# mcu_core.net
KiCad netlist of a schematic drawn in Altium Designer
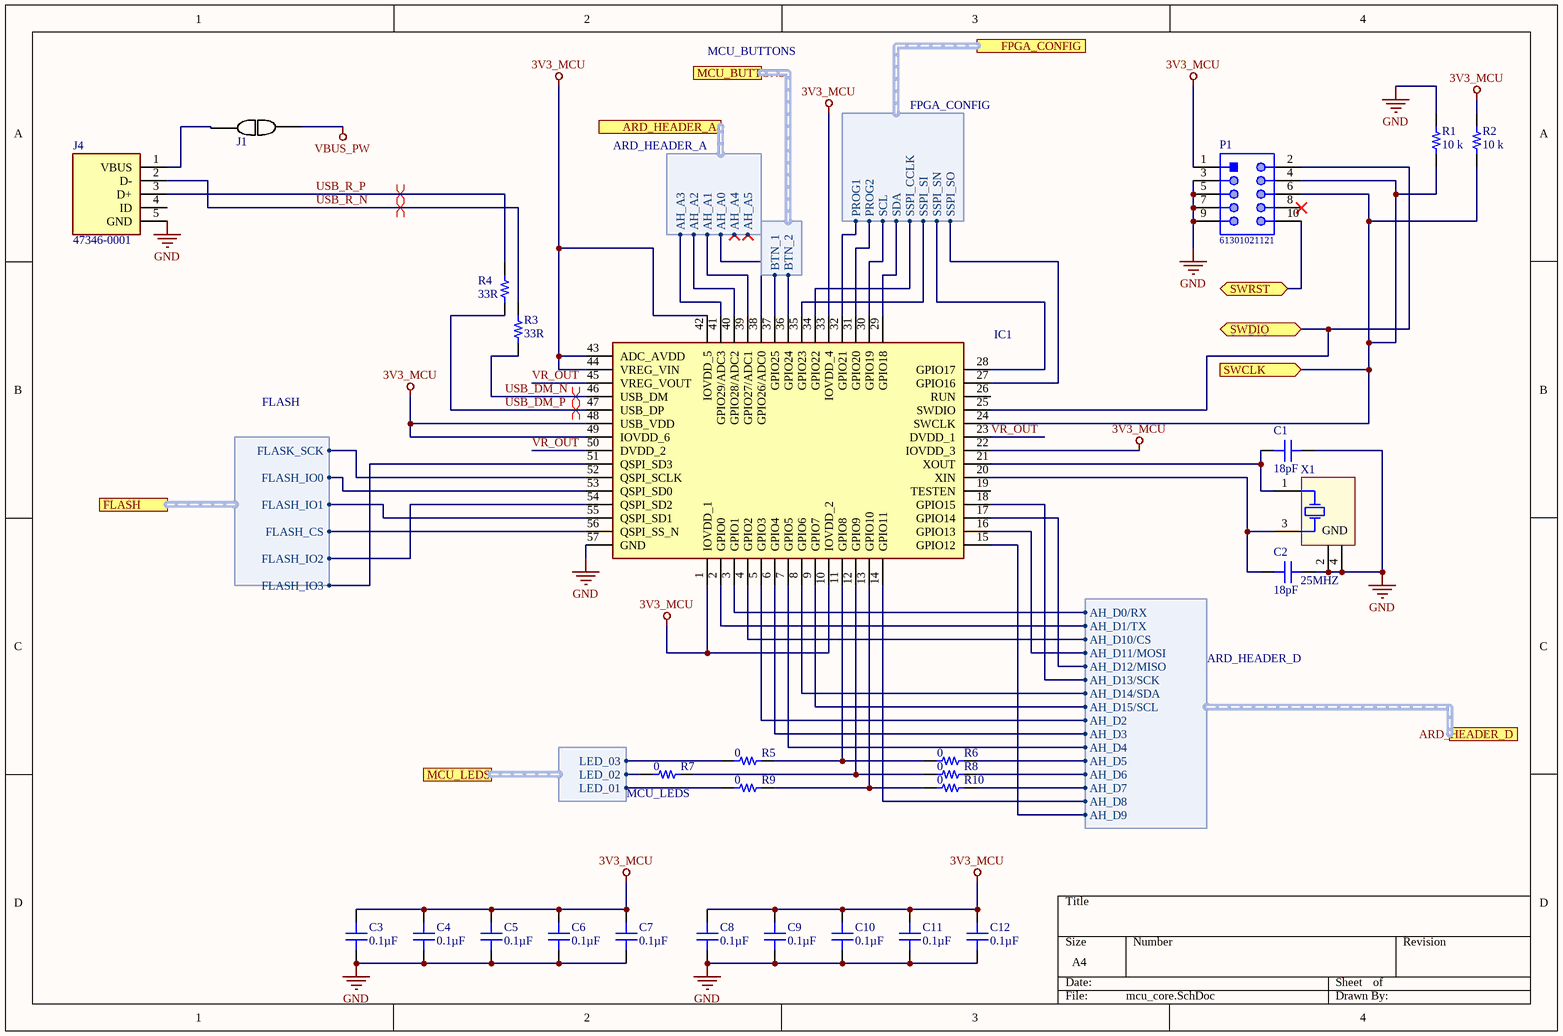
[diagram p0: mcu_core.SchDoc]

(export (version "E")
  (design (tool "Eeschema 10.0.6"))
  (components
    (comp (ref "C1")
      (value "18pF")
      (footprint "CAP 0603_1608")
      (description "CAP CER 18PF 10V C0G/NP0 0603")
      (fields
        (field (name "PART NUMBER") "VJ0603A180FXQCW1BC")
        (field (name "MANUFACTURER") "Vishay Vitramon")
      )
      (libsource (lib "Celestial Altium Library - altium_library (2)") (part "Capacitor"))
    )
    (comp (ref "C2")
      (value "18pF")
      (footprint "CAP 0603_1608")
      (description "CAP CER 18PF 10V C0G/NP0 0603")
      (fields
        (field (name "PART NUMBER") "VJ0603A180FXQCW1BC")
        (field (name "MANUFACTURER") "Vishay Vitramon")
      )
      (libsource (lib "Celestial Altium Library - altium_library (2)") (part "Capacitor"))
    )
    (comp (ref "C3")
      (value "0.1µF")
      (footprint "CAP 0603_1608")
      (description "CAP CER 0.1UF 50V X7R 0603")
      (fields (field (name "PART NUMBER") "C0603C104K5RAC7411") (field (name "MANUFACTURER") "KEMET"))
      (libsource (lib "Celestial Altium Library - altium_library (2)") (part "Capacitor"))
    )
    (comp (ref "C4")
      (value "0.1µF")
      (footprint "CAP 0603_1608")
      (description "CAP CER 0.1UF 50V X7R 0603")
      (fields (field (name "PART NUMBER") "C0603C104K5RAC7411") (field (name "MANUFACTURER") "KEMET"))
      (libsource (lib "Celestial Altium Library - altium_library (2)") (part "Capacitor"))
    )
    (comp (ref "C5")
      (value "0.1µF")
      (footprint "CAP 0603_1608")
      (description "CAP CER 0.1UF 50V X7R 0603")
      (fields (field (name "PART NUMBER") "C0603C104K5RAC7411") (field (name "MANUFACTURER") "KEMET"))
      (libsource (lib "Celestial Altium Library - altium_library (2)") (part "Capacitor"))
    )
    (comp (ref "C6")
      (value "0.1µF")
      (footprint "CAP 0603_1608")
      (description "CAP CER 0.1UF 50V X7R 0603")
      (fields (field (name "PART NUMBER") "C0603C104K5RAC7411") (field (name "MANUFACTURER") "KEMET"))
      (libsource (lib "Celestial Altium Library - altium_library (2)") (part "Capacitor"))
    )
    (comp (ref "C7")
      (value "0.1µF")
      (footprint "CAP 0603_1608")
      (description "CAP CER 0.1UF 50V X7R 0603")
      (fields (field (name "PART NUMBER") "C0603C104K5RAC7411") (field (name "MANUFACTURER") "KEMET"))
      (libsource (lib "Celestial Altium Library - altium_library (2)") (part "Capacitor"))
    )
    (comp (ref "C8")
      (value "0.1µF")
      (footprint "CAP 0603_1608")
      (description "CAP CER 0.1UF 50V X7R 0603")
      (fields (field (name "PART NUMBER") "C0603C104K5RAC7411") (field (name "MANUFACTURER") "KEMET"))
      (libsource (lib "Celestial Altium Library - altium_library (2)") (part "Capacitor"))
    )
    (comp (ref "C9")
      (value "0.1µF")
      (footprint "CAP 0603_1608")
      (description "CAP CER 0.1UF 50V X7R 0603")
      (fields (field (name "PART NUMBER") "C0603C104K5RAC7411") (field (name "MANUFACTURER") "KEMET"))
      (libsource (lib "Celestial Altium Library - altium_library (2)") (part "Capacitor"))
    )
    (comp (ref "C10")
      (value "0.1µF")
      (footprint "CAP 0603_1608")
      (description "CAP CER 0.1UF 50V X7R 0603")
      (fields (field (name "PART NUMBER") "C0603C104K5RAC7411") (field (name "MANUFACTURER") "KEMET"))
      (libsource (lib "Celestial Altium Library - altium_library (2)") (part "Capacitor"))
    )
    (comp (ref "C11")
      (value "0.1µF")
      (footprint "CAP 0603_1608")
      (description "CAP CER 0.1UF 50V X7R 0603")
      (fields (field (name "PART NUMBER") "C0603C104K5RAC7411") (field (name "MANUFACTURER") "KEMET"))
      (libsource (lib "Celestial Altium Library - altium_library (2)") (part "Capacitor"))
    )
    (comp (ref "C12")
      (value "0.1µF")
      (footprint "CAP 0603_1608")
      (description "CAP CER 0.1UF 50V X7R 0603")
      (fields (field (name "PART NUMBER") "C0603C104K5RAC7411") (field (name "MANUFACTURER") "KEMET"))
      (libsource (lib "Celestial Altium Library - altium_library (2)") (part "Capacitor"))
    )
    (comp (ref "IC1")
      (value "~")
      (footprint "QFN40P700X700X90-57N-D")
      (description "Integrated Circuit")
      (fields (field (name "MANUFACTURER_PART_NUMBER") "RP2040"))
      (libsource (lib "SamacSys") (part "RP2040"))
    )
    (comp (ref "J1")
      (value "103185-2")
      (footprint "HDRV2W89P0X254_1X2_467X234X820P")
      (description "02 MODII HDR SRST B/A .100CL")
      (libsource (lib "SamacSys") (part "103185-2"))
    )
    (comp (ref "J4")
      (value "47346-0001")
      (footprint "SamacSys:47346-0001")
      (description "Connector")
      (fields (field (name "MOUSER PART NUMBER") "538-47346-0001"))
      (libsource (lib "SamacSys") (part "47346-0001"))
    )
    (comp (ref "P1")
      (value "61301021121")
      (footprint "61301021121")
      (description "THT Vertical Pin Header WR-PHD, Pitch 2.54 mm, Dual Row, 10 pins")
      (fields (field (name "MANUFACTURER") "Wurth Elektronik") (field (name "PUBLISHER") "WurthElektronik"))
      (libsource (lib "Altium Content Vault") (part "WE-CN-2P-M-R10"))
    )
    (comp (ref "R1")
      (value "10 k")
      (footprint "RES 0603_1608")
      (description "RES 10K OHM 0.1% 1/16W 0603")
      (fields
        (field (name "PART NUMBER") "RNCS0603BKE10K0")
        (field (name "MANUFACTURER") "Stackpole Electronics Inc")
      )
      (libsource (lib "Celestial Altium Library - altium_library (2)") (part "Resistor"))
    )
    (comp (ref "R2")
      (value "10 k")
      (footprint "RES 0603_1608")
      (description "RES 10K OHM 0.1% 1/16W 0603")
      (fields
        (field (name "PART NUMBER") "RNCS0603BKE10K0")
        (field (name "MANUFACTURER") "Stackpole Electronics Inc")
      )
      (libsource (lib "Celestial Altium Library - altium_library (2)") (part "Resistor"))
    )
    (comp (ref "R3")
      (value "33R")
      (footprint "RES 0603_1608")
      (description "RES SMD 33 OHM 0.1% 1/16W 0603")
      (fields
        (field (name "PART NUMBER") "CPF0603B33RE")
        (field (name "MANUFACTURER") "TE Connectivity Passive Product")
      )
      (libsource (lib "Celestial Altium Library - altium_library (2)") (part "Resistor"))
    )
    (comp (ref "R4")
      (value "33R")
      (footprint "RES 0603_1608")
      (description "RES SMD 33 OHM 0.1% 1/16W 0603")
      (fields
        (field (name "PART NUMBER") "CPF0603B33RE")
        (field (name "MANUFACTURER") "TE Connectivity Passive Product")
      )
      (libsource (lib "Celestial Altium Library - altium_library (2)") (part "Resistor"))
    )
    (comp (ref "R5")
      (value "0")
      (footprint "RES 0603_1608")
      (description "RES 0 OHM JUMPER 0603")
      (fields
        (field (name "PART NUMBER") "TLRZ1JTTD")
        (field (name "MANUFACTURER") "KOA Speer Electronics, Inc.")
      )
      (libsource (lib "Celestial Altium Library - altium_library (2)") (part "Resistor"))
    )
    (comp (ref "R6")
      (value "0")
      (footprint "RES 0603_1608")
      (description "RES 0 OHM JUMPER 0603")
      (fields
        (field (name "PART NUMBER") "TLRZ1JTTD")
        (field (name "MANUFACTURER") "KOA Speer Electronics, Inc.")
      )
      (libsource (lib "Celestial Altium Library - altium_library (2)") (part "Resistor"))
    )
    (comp (ref "R7")
      (value "0")
      (footprint "RES 0603_1608")
      (description "RES 0 OHM JUMPER 0603")
      (fields
        (field (name "PART NUMBER") "TLRZ1JTTD")
        (field (name "MANUFACTURER") "KOA Speer Electronics, Inc.")
      )
      (libsource (lib "Celestial Altium Library - altium_library (2)") (part "Resistor"))
    )
    (comp (ref "R8")
      (value "0")
      (footprint "RES 0603_1608")
      (description "RES 0 OHM JUMPER 0603")
      (fields
        (field (name "PART NUMBER") "TLRZ1JTTD")
        (field (name "MANUFACTURER") "KOA Speer Electronics, Inc.")
      )
      (libsource (lib "Celestial Altium Library - altium_library (2)") (part "Resistor"))
    )
    (comp (ref "R9")
      (value "0")
      (footprint "RES 0603_1608")
      (description "RES 0 OHM JUMPER 0603")
      (fields
        (field (name "PART NUMBER") "TLRZ1JTTD")
        (field (name "MANUFACTURER") "KOA Speer Electronics, Inc.")
      )
      (libsource (lib "Celestial Altium Library - altium_library (2)") (part "Resistor"))
    )
    (comp (ref "R10")
      (value "0")
      (footprint "RES 0603_1608")
      (description "RES 0 OHM JUMPER 0603")
      (fields
        (field (name "PART NUMBER") "TLRZ1JTTD")
        (field (name "MANUFACTURER") "KOA Speer Electronics, Inc.")
      )
      (libsource (lib "Celestial Altium Library - altium_library (2)") (part "Resistor"))
    )
    (comp (ref "X1")
      (value "25MHZ")
      (footprint "ABRA-ABMM2-4_V")
      (fields (field (name "MANUFACTURER") "Abracon") (field (name "PARTNUMBER") "ABMM2-8.000MHZ-E2-T"))
      (libsource (lib "Altium Content Vault") (part "ABRA-XTAL_1-3-4"))
    )
  )
  (nets
    (net (code "7") (name "/AH_A0") (class "Default")
      (node (ref "IC1") (pin "38") (pinfunction "GPIO26/ADC0_38") (pintype "passive"))
    )
    (net (code "8") (name "/AH_A1") (class "Default")
      (node (ref "IC1") (pin "39") (pinfunction "GPIO27/ADC1_39") (pintype "passive"))
    )
    (net (code "9") (name "/AH_A2") (class "Default")
      (node (ref "IC1") (pin "40") (pinfunction "GPIO28/ADC2_40") (pintype "passive"))
    )
    (net (code "10") (name "/AH_A3") (class "Default")
      (node (ref "IC1") (pin "41") (pinfunction "GPIO29/ADC3_41") (pintype "passive"))
    )
    (net (code "11") (name "/AH_D0{slash}RX") (class "Default")
      (node (ref "IC1") (pin "3") (pinfunction "GPIO1_3") (pintype "passive"))
    )
    (net (code "12") (name "/AH_D1{slash}TX") (class "Default")
      (node (ref "IC1") (pin "2") (pinfunction "GPIO0_2") (pintype "passive"))
    )
    (net (code "13") (name "/AH_D2") (class "Default")
      (node (ref "IC1") (pin "5") (pinfunction "GPIO3_5") (pintype "passive"))
    )
    (net (code "14") (name "/AH_D3") (class "Default")
      (node (ref "IC1") (pin "6") (pinfunction "GPIO4_6") (pintype "passive"))
    )
    (net (code "15") (name "/AH_D4") (class "Default")
      (node (ref "IC1") (pin "7") (pinfunction "GPIO5_7") (pintype "passive"))
    )
    (net (code "16") (name "/AH_D5") (class "Default")
      (node (ref "R6") (pin "2") (pinfunction "2_2") (pintype "passive"))
    )
    (net (code "17") (name "/AH_D6") (class "Default")
      (node (ref "R8") (pin "2") (pinfunction "2_2") (pintype "passive"))
    )
    (net (code "18") (name "/AH_D7") (class "Default")
      (node (ref "R10") (pin "2") (pinfunction "2_2") (pintype "passive"))
    )
    (net (code "19") (name "/AH_D8") (class "Default")
      (node (ref "IC1") (pin "14") (pinfunction "GPIO11_14") (pintype "passive"))
    )
    (net (code "20") (name "/AH_D9") (class "Default")
      (node (ref "IC1") (pin "15") (pinfunction "GPIO12_15") (pintype "passive"))
    )
    (net (code "21") (name "/AH_D10{slash}CS") (class "Default")
      (node (ref "IC1") (pin "4") (pinfunction "GPIO2_4") (pintype "passive"))
    )
    (net (code "22") (name "/AH_D11{slash}MOSI") (class "Default")
      (node (ref "IC1") (pin "16") (pinfunction "GPIO13_16") (pintype "passive"))
    )
    (net (code "23") (name "/AH_D12{slash}MISO") (class "Default")
      (node (ref "IC1") (pin "17") (pinfunction "GPIO14_17") (pintype "passive"))
    )
    (net (code "24") (name "/AH_D13{slash}SCK") (class "Default")
      (node (ref "IC1") (pin "18") (pinfunction "GPIO15_18") (pintype "passive"))
    )
    (net (code "25") (name "/AH_D14{slash}SDA") (class "Default")
      (node (ref "IC1") (pin "8") (pinfunction "GPIO6_8") (pintype "passive"))
    )
    (net (code "26") (name "/AH_D15{slash}SCL") (class "Default")
      (node (ref "IC1") (pin "9") (pinfunction "GPIO7_9") (pintype "passive"))
    )
    (net (code "27") (name "/BTN_1") (class "Default")
      (node (ref "IC1") (pin "37") (pinfunction "GPIO25_37") (pintype "passive"))
    )
    (net (code "28") (name "/BTN_2") (class "Default")
      (node (ref "IC1") (pin "36") (pinfunction "GPIO24_36") (pintype "passive"))
    )
    (net (code "29") (name "/FLASH_CS") (class "Default")
      (node (ref "IC1") (pin "56") (pinfunction "QSPI_SS_N_56") (pintype "passive"))
    )
    (net (code "30") (name "/FLASH_IO0") (class "Default")
      (node (ref "IC1") (pin "53") (pinfunction "QSPI_SD0_53") (pintype "passive"))
    )
    (net (code "31") (name "/FLASH_IO1") (class "Default")
      (node (ref "IC1") (pin "55") (pinfunction "QSPI_SD1_55") (pintype "passive"))
    )
    (net (code "32") (name "/FLASH_IO2") (class "Default")
      (node (ref "IC1") (pin "54") (pinfunction "QSPI_SD2_54") (pintype "passive"))
    )
    (net (code "33") (name "/FLASH_IO3") (class "Default")
      (node (ref "IC1") (pin "51") (pinfunction "QSPI_SD3_51") (pintype "passive"))
    )
    (net (code "34") (name "/FLASK_SCK") (class "Default")
      (node (ref "IC1") (pin "52") (pinfunction "QSPI_SCLK_52") (pintype "passive"))
    )
    (net (code "35") (name "/LED_01") (class "Default")
      (node (ref "R9") (pin "1") (pinfunction "1_1") (pintype "passive"))
    )
    (net (code "36") (name "/LED_02") (class "Default")
      (node (ref "R7") (pin "1") (pinfunction "1_1") (pintype "passive"))
    )
    (net (code "37") (name "/LED_03") (class "Default")
      (node (ref "R5") (pin "1") (pinfunction "1_1") (pintype "passive"))
    )
    (net (code "38") (name "/PROG1") (class "Default")
      (node (ref "IC1") (pin "32") (pinfunction "GPIO21_32") (pintype "passive"))
    )
    (net (code "39") (name "/PROG2") (class "Default")
      (node (ref "IC1") (pin "31") (pinfunction "GPIO20_31") (pintype "passive"))
    )
    (net (code "40") (name "/SCL") (class "Default")
      (node (ref "IC1") (pin "30") (pinfunction "GPIO19_30") (pintype "passive"))
    )
    (net (code "41") (name "/SDA") (class "Default")
      (node (ref "IC1") (pin "29") (pinfunction "GPIO18_29") (pintype "passive"))
    )
    (net (code "42") (name "/SSPI_CCLK") (class "Default")
      (node (ref "IC1") (pin "34") (pinfunction "GPIO22_34") (pintype "passive"))
    )
    (net (code "43") (name "/SSPI_SI") (class "Default")
      (node (ref "IC1") (pin "35") (pinfunction "GPIO23_35") (pintype "passive"))
    )
    (net (code "44") (name "/SSPI_SN") (class "Default")
      (node (ref "IC1") (pin "28") (pinfunction "GPIO17_28") (pintype "passive"))
    )
    (net (code "45") (name "/SSPI_SO") (class "Default")
      (node (ref "IC1") (pin "27") (pinfunction "GPIO16_27") (pintype "passive"))
    )
    (net (code "46") (name "/SWCLK") (class "Default")
      (node (ref "IC1") (pin "24") (pinfunction "SWCLK_24") (pintype "passive"))
      (node (ref "P1") (pin "4") (pinfunction "4_4") (pintype "passive"))
      (node (ref "P1") (pin "6") (pinfunction "6_6") (pintype "passive"))
      (node (ref "R1") (pin "1") (pinfunction "1_1") (pintype "passive"))
      (node (ref "R2") (pin "1") (pinfunction "1_1") (pintype "passive"))
    )
    (net (code "47") (name "/SWDIO") (class "Default")
      (node (ref "IC1") (pin "25") (pinfunction "SWDIO_25") (pintype "passive"))
      (node (ref "P1") (pin "2") (pinfunction "2_2") (pintype "passive"))
    )
    (net (code "48") (name "/SWRST") (class "Default")
      (node (ref "P1") (pin "10") (pinfunction "10_10") (pintype "passive"))
    )
    (net (code "49") (name "/USB_DM_N") (class "Default")
      (node (ref "IC1") (pin "46") (pinfunction "USB_DM_46") (pintype "passive"))
      (node (ref "R3") (pin "1") (pinfunction "1_1") (pintype "passive"))
    )
    (net (code "50") (name "/USB_DM_P") (class "Default")
      (node (ref "IC1") (pin "47") (pinfunction "USB_DP_47") (pintype "passive"))
      (node (ref "R4") (pin "2") (pinfunction "2_2") (pintype "passive"))
    )
    (net (code "51") (name "/USB_R_N") (class "Default")
      (node (ref "J4") (pin "2") (pinfunction "D-_2") (pintype "passive"))
      (node (ref "R3") (pin "2") (pinfunction "2_2") (pintype "passive"))
    )
    (net (code "52") (name "/USB_R_P") (class "Default")
      (node (ref "J4") (pin "3") (pinfunction "D+_3") (pintype "passive"))
      (node (ref "R4") (pin "1") (pinfunction "1_1") (pintype "passive"))
    )
    (net (code "53") (name "/VR_OUT") (class "Default")
      (node (ref "IC1") (pin "23") (pinfunction "DVDD_1_23") (pintype "passive"))
      (node (ref "IC1") (pin "45") (pinfunction "VREG_VOUT_45") (pintype "passive"))
      (node (ref "IC1") (pin "50") (pinfunction "DVDD_2_50") (pintype "passive"))
    )
    (net (code "60") (name "3V3_MCU") (class "Default")
      (node (ref "C10") (pin "2") (pinfunction "2_2") (pintype "passive"))
      (node (ref "C11") (pin "2") (pinfunction "2_2") (pintype "passive"))
      (node (ref "C12") (pin "2") (pinfunction "2_2") (pintype "passive"))
      (node (ref "C3") (pin "2") (pinfunction "2_2") (pintype "passive"))
      (node (ref "C4") (pin "2") (pinfunction "2_2") (pintype "passive"))
      (node (ref "C5") (pin "2") (pinfunction "2_2") (pintype "passive"))
      (node (ref "C6") (pin "2") (pinfunction "2_2") (pintype "passive"))
      (node (ref "C7") (pin "2") (pinfunction "2_2") (pintype "passive"))
      (node (ref "C8") (pin "2") (pinfunction "2_2") (pintype "passive"))
      (node (ref "C9") (pin "2") (pinfunction "2_2") (pintype "passive"))
      (node (ref "IC1") (pin "1") (pinfunction "IOVDD_1_1") (pintype "passive"))
      (node (ref "IC1") (pin "10") (pinfunction "IOVDD_2_10") (pintype "passive"))
      (node (ref "IC1") (pin "22") (pinfunction "IOVDD_3_22") (pintype "passive"))
      (node (ref "IC1") (pin "33") (pinfunction "IOVDD_4_33") (pintype "passive"))
      (node (ref "IC1") (pin "42") (pinfunction "IOVDD_5_42") (pintype "passive"))
      (node (ref "IC1") (pin "43") (pinfunction "ADC_AVDD_43") (pintype "passive"))
      (node (ref "IC1") (pin "44") (pinfunction "VREG_VIN_44") (pintype "passive"))
      (node (ref "IC1") (pin "48") (pinfunction "USB_VDD_48") (pintype "passive"))
      (node (ref "IC1") (pin "49") (pinfunction "IOVDD_6_49") (pintype "passive"))
      (node (ref "P1") (pin "1") (pinfunction "1_1") (pintype "passive"))
      (node (ref "R2") (pin "2") (pinfunction "2_2") (pintype "passive"))
    )
    (net (code "61") (name "GND") (class "Default")
      (node (ref "C1") (pin "1") (pinfunction "1_1") (pintype "passive"))
      (node (ref "C10") (pin "1") (pinfunction "1_1") (pintype "passive"))
      (node (ref "C11") (pin "1") (pinfunction "1_1") (pintype "passive"))
      (node (ref "C12") (pin "1") (pinfunction "1_1") (pintype "passive"))
      (node (ref "C2") (pin "1") (pinfunction "1_1") (pintype "passive"))
      (node (ref "C3") (pin "1") (pinfunction "1_1") (pintype "passive"))
      (node (ref "C4") (pin "1") (pinfunction "1_1") (pintype "passive"))
      (node (ref "C5") (pin "1") (pinfunction "1_1") (pintype "passive"))
      (node (ref "C6") (pin "1") (pinfunction "1_1") (pintype "passive"))
      (node (ref "C7") (pin "1") (pinfunction "1_1") (pintype "passive"))
      (node (ref "C8") (pin "1") (pinfunction "1_1") (pintype "passive"))
      (node (ref "C9") (pin "1") (pinfunction "1_1") (pintype "passive"))
      (node (ref "IC1") (pin "57") (pinfunction "GND_57") (pintype "passive"))
      (node (ref "J4") (pin "5") (pinfunction "GND_5") (pintype "passive"))
      (node (ref "P1") (pin "3") (pinfunction "3_3") (pintype "passive"))
      (node (ref "P1") (pin "5") (pinfunction "5_5") (pintype "passive"))
      (node (ref "P1") (pin "7") (pinfunction "7_7") (pintype "passive"))
      (node (ref "P1") (pin "9") (pinfunction "9_9") (pintype "passive"))
      (node (ref "R1") (pin "2") (pinfunction "2_2") (pintype "passive"))
      (node (ref "X1") (pin "2") (pinfunction "GND_2") (pintype "power_in"))
      (node (ref "X1") (pin "4") (pinfunction "GND_4") (pintype "power_in"))
    )
    (net (code "62") (name "Net-(IC1-GPIO8)") (class "Default")
      (node (ref "IC1") (pin "11") (pinfunction "GPIO8_11") (pintype "passive"))
      (node (ref "R5") (pin "2") (pinfunction "2_2") (pintype "passive"))
      (node (ref "R6") (pin "1") (pinfunction "1_1") (pintype "passive"))
    )
    (net (code "63") (name "Net-(IC1-GPIO9)") (class "Default")
      (node (ref "IC1") (pin "12") (pinfunction "GPIO9_12") (pintype "passive"))
      (node (ref "R7") (pin "2") (pinfunction "2_2") (pintype "passive"))
      (node (ref "R8") (pin "1") (pinfunction "1_1") (pintype "passive"))
    )
    (net (code "64") (name "Net-(IC1-GPIO10)") (class "Default")
      (node (ref "IC1") (pin "13") (pinfunction "GPIO10_13") (pintype "passive"))
      (node (ref "R10") (pin "1") (pinfunction "1_1") (pintype "passive"))
      (node (ref "R9") (pin "2") (pinfunction "2_2") (pintype "passive"))
    )
    (net (code "65") (name "Net-(IC1-XIN)") (class "Default")
      (node (ref "C2") (pin "2") (pinfunction "2_2") (pintype "passive"))
      (node (ref "IC1") (pin "20") (pinfunction "XIN_20") (pintype "passive"))
      (node (ref "X1") (pin "3") (pinfunction "X2_3") (pintype "passive"))
    )
    (net (code "66") (name "Net-(IC1-XOUT)") (class "Default")
      (node (ref "C1") (pin "2") (pinfunction "2_2") (pintype "passive"))
      (node (ref "IC1") (pin "21") (pinfunction "XOUT_21") (pintype "passive"))
      (node (ref "X1") (pin "1") (pinfunction "X1_1") (pintype "passive"))
    )
    (net (code "67") (name "Net-(J4-VBUS)") (class "Default")
      (node (ref "J1") (pin "2") (pinfunction "2_2") (pintype "passive"))
      (node (ref "J4") (pin "1") (pinfunction "VBUS_1") (pintype "passive"))
    )
    (net (code "68") (name "VBUS_PW") (class "Default")
      (node (ref "J1") (pin "1") (pinfunction "1_1") (pintype "passive"))
    )
    (net (code "69") (name "unconnected-(IC1-RUN-Pad26)") (class "Default")
      (node (ref "IC1") (pin "26") (pinfunction "RUN_26") (pintype "passive"))
    )
    (net (code "70") (name "unconnected-(IC1-TESTEN-Pad19)") (class "Default")
      (node (ref "IC1") (pin "19") (pinfunction "TESTEN_19") (pintype "passive"))
    )
    (net (code "71") (name "unconnected-(J4-ID-Pad4)") (class "Default")
      (node (ref "J4") (pin "4") (pinfunction "ID_4") (pintype "passive"))
    )
    (net (code "72") (name "unconnected-(P1-Pad8)") (class "Default")
      (node (ref "P1") (pin "8") (pinfunction "8_8") (pintype "passive+no_connect"))
    )
  )
)
